# dual-led-wireless-dimmer-tx.net
KiCad netlist of a schematic drawn in EAGLE
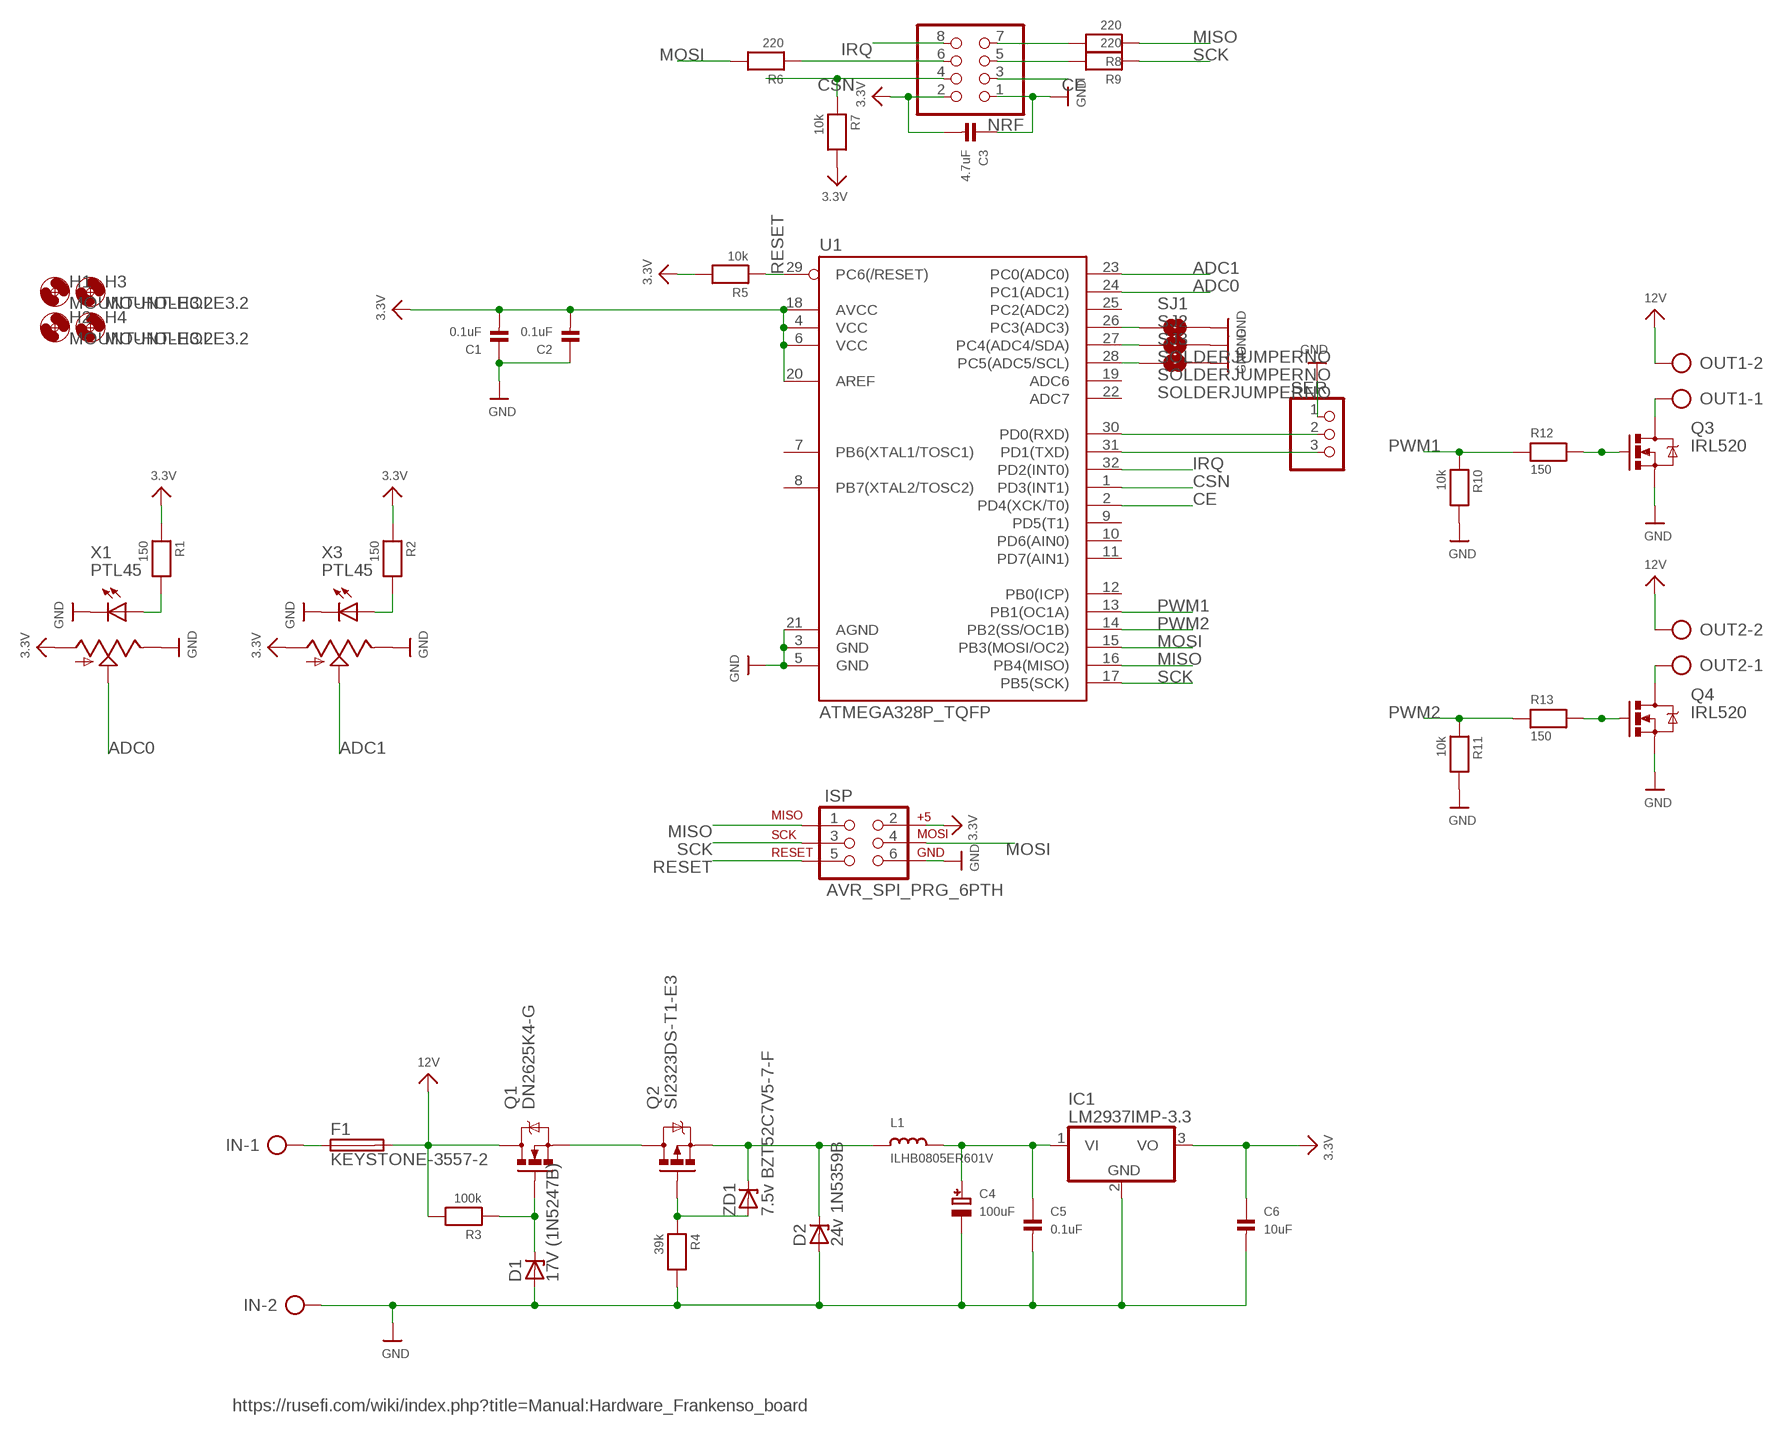
[diagram p0: schematic, sheet 1]

(export (version "E")
  (design (tool "Eeschema 10.0.6"))
  (components
    (comp (ref "C1")
      (value "0.1uF")
      (footprint "eagle-import:0805")
      (libsource (lib "eagle-import") (part "CAP_CERAMIC0805"))
    )
    (comp (ref "C2")
      (value "0.1uF")
      (footprint "eagle-import:0805")
      (libsource (lib "eagle-import") (part "CAP_CERAMIC0805"))
    )
    (comp (ref "C3")
      (value "4.7uF")
      (footprint "eagle-import:0805")
      (libsource (lib "eagle-import") (part "CAP_CERAMIC0805"))
    )
    (comp (ref "C4")
      (value "100uF")
      (footprint "eagle-import:PANASONIC_D")
      (libsource (lib "eagle-import") (part "CAP_ELECTROLYTICPANASONIC_D"))
    )
    (comp (ref "C5")
      (value "0.1uF")
      (footprint "eagle-import:0805")
      (libsource (lib "eagle-import") (part "CAP_CERAMIC0805"))
    )
    (comp (ref "C6")
      (value "10uF")
      (footprint "eagle-import:0805")
      (libsource (lib "eagle-import") (part "CAP_CERAMIC0805"))
    )
    (comp (ref "D1")
      (value "17V (1N5247B)")
      (footprint "eagle-import:ZDIO-5")
      (libsource (lib "eagle-import") (part "ZENER-DIODEZD-5"))
    )
    (comp (ref "D2")
      (value "24v 1N5359B")
      (footprint "eagle-import:DO41Z10")
      (libsource (lib "eagle-import") (part "ZPY"))
    )
    (comp (ref "F1")
      (value "KEYSTONE-3557-2")
      (footprint "eagle-import:KEYSTONE-3557-2")
      (libsource (lib "eagle-import") (part "KEYSTONE-3557-2"))
    )
    (comp (ref "H1")
      (value "MOUNT-HOLE3.2")
      (footprint "eagle-import:3,2")
      (libsource (lib "eagle-import") (part "MOUNT-HOLE3.2"))
    )
    (comp (ref "H2")
      (value "MOUNT-HOLE3.2")
      (footprint "eagle-import:3,2")
      (libsource (lib "eagle-import") (part "MOUNT-HOLE3.2"))
    )
    (comp (ref "H3")
      (value "MOUNT-HOLE3.2")
      (footprint "eagle-import:3,2")
      (libsource (lib "eagle-import") (part "MOUNT-HOLE3.2"))
    )
    (comp (ref "H4")
      (value "MOUNT-HOLE3.2")
      (footprint "eagle-import:3,2")
      (libsource (lib "eagle-import") (part "MOUNT-HOLE3.2"))
    )
    (comp (ref "IC1")
      (value "LM2937IMP-3.3")
      (footprint "eagle-import:TO263-3")
      (libsource (lib "eagle-import") (part "LM2937"))
    )
    (comp (ref "IN")
      (value "AK500/2-H")
      (footprint "eagle-import:AK500_2-H")
      (libsource (lib "eagle-import") (part "AK500/2-H"))
    )
    (comp (ref "ISP")
      (value "AVR_SPI_PRG_6PTH")
      (footprint "eagle-import:2X3")
      (libsource (lib "eagle-import") (part "AVR_SPI_PRG_6PTH"))
    )
    (comp (ref "L1")
      (value "ILHB0805ER601V")
      (footprint "eagle-import:0805")
      (libsource (lib "eagle-import") (part "INDUCTOR0805"))
    )
    (comp (ref "NRF")
      (value "PINHD-2X4")
      (footprint "eagle-import:2X04")
      (libsource (lib "eagle-import") (part "PINHD-2X4"))
    )
    (comp (ref "OUT1")
      (value "AK500/2-H")
      (footprint "eagle-import:AK500_2-H")
      (libsource (lib "eagle-import") (part "AK500/2-H"))
    )
    (comp (ref "OUT2")
      (value "AK500/2-H")
      (footprint "eagle-import:AK500_2-H")
      (libsource (lib "eagle-import") (part "AK500/2-H"))
    )
    (comp (ref "Q1")
      (value "DN2625K4-G")
      (footprint "eagle-import:DPAK")
      (libsource (lib "eagle-import") (part "MOSFET-NCHANNELFDD8780"))
    )
    (comp (ref "Q2")
      (value "SI2323DS-T1-E3")
      (footprint "eagle-import:SOT23-3")
      (libsource (lib "eagle-import") (part "MOSFET-PCHANNEL"))
    )
    (comp (ref "Q3")
      (value "IRL520")
      (footprint "eagle-import:TO220V")
      (libsource (lib "eagle-import") (part "keves-ng_1429743_MOSFET-NCHANNELFQP30N06L"))
    )
    (comp (ref "Q4")
      (value "IRL520")
      (footprint "eagle-import:TO220V")
      (libsource (lib "eagle-import") (part "keves-ng_1429743_MOSFET-NCHANNELFQP30N06L"))
    )
    (comp (ref "R1")
      (value "150")
      (footprint "eagle-import:0805")
      (libsource (lib "eagle-import") (part "RESISTOR0805"))
    )
    (comp (ref "R2")
      (value "150")
      (footprint "eagle-import:0805")
      (libsource (lib "eagle-import") (part "RESISTOR0805"))
    )
    (comp (ref "R3")
      (value "100k")
      (footprint "eagle-import:0805")
      (libsource (lib "eagle-import") (part "RESISTOR0805"))
    )
    (comp (ref "R4")
      (value "39k")
      (footprint "eagle-import:0805")
      (libsource (lib "eagle-import") (part "RESISTOR0805"))
    )
    (comp (ref "R5")
      (value "10k")
      (footprint "eagle-import:0805")
      (libsource (lib "eagle-import") (part "RESISTOR0805"))
    )
    (comp (ref "R6")
      (value "220")
      (footprint "eagle-import:0805")
      (libsource (lib "eagle-import") (part "RESISTOR0805"))
    )
    (comp (ref "R7")
      (value "10k")
      (footprint "eagle-import:0805")
      (libsource (lib "eagle-import") (part "RESISTOR0805"))
    )
    (comp (ref "R8")
      (value "220")
      (footprint "eagle-import:0805")
      (libsource (lib "eagle-import") (part "RESISTOR0805"))
    )
    (comp (ref "R9")
      (value "220")
      (footprint "eagle-import:0805")
      (libsource (lib "eagle-import") (part "RESISTOR0805"))
    )
    (comp (ref "R10")
      (value "10k")
      (footprint "eagle-import:0805")
      (libsource (lib "eagle-import") (part "RESISTOR0805"))
    )
    (comp (ref "R11")
      (value "10k")
      (footprint "eagle-import:0805")
      (libsource (lib "eagle-import") (part "RESISTOR0805"))
    )
    (comp (ref "R12")
      (value "150")
      (footprint "eagle-import:0805")
      (libsource (lib "eagle-import") (part "RESISTOR0805"))
    )
    (comp (ref "R13")
      (value "150")
      (footprint "eagle-import:0805")
      (libsource (lib "eagle-import") (part "RESISTOR0805"))
    )
    (comp (ref "SER")
      (value "PINHD-1X3")
      (footprint "eagle-import:1X03")
      (libsource (lib "eagle-import") (part "PINHD-1X3"))
    )
    (comp (ref "SJ1")
      (value "SOLDERJUMPERNO")
      (footprint "eagle-import:SJ_2S-NO")
      (libsource (lib "eagle-import") (part "SOLDERJUMPERNO"))
    )
    (comp (ref "SJ2")
      (value "SOLDERJUMPERNO")
      (footprint "eagle-import:SJ_2S-NO")
      (libsource (lib "eagle-import") (part "SOLDERJUMPERNO"))
    )
    (comp (ref "SJ3")
      (value "SOLDERJUMPERNO")
      (footprint "eagle-import:SJ_2S-NO")
      (libsource (lib "eagle-import") (part "SOLDERJUMPERNO"))
    )
    (comp (ref "U1")
      (value "ATMEGA328P_TQFP")
      (footprint "eagle-import:TQFP32-08")
      (libsource (lib "eagle-import") (part "ATMEGA328P_TQFP"))
    )
    (comp (ref "X1")
      (value "PTL45")
      (footprint "eagle-import:BOURNS-PTL45")
      (fields (field (name "SPICEPREFIX") "C"))
      (libsource (lib "eagle-import") (part "PTL45"))
    )
    (comp (ref "X3")
      (value "PTL45")
      (footprint "eagle-import:BOURNS-PTL45")
      (libsource (lib "eagle-import") (part "PTL45"))
    )
    (comp (ref "ZD1")
      (value "7.5v BZT52C7V5-7-F")
      (footprint "eagle-import:SOD123")
      (libsource (lib "eagle-import") (part "ZD-SOD123"))
    )
  )
  (nets
    (net (code "1") (name "/ADC0") (class "Default")
      (node (ref "U1") (pin "24") (pinfunction "PC1(ADC1)_24") (pintype "bidirectional"))
      (node (ref "X1") (pin "2") (pinfunction "S_2") (pintype "passive"))
    )
    (net (code "2") (name "/ADC1") (class "Default")
      (node (ref "U1") (pin "23") (pinfunction "PC0(ADC0)_23") (pintype "bidirectional"))
      (node (ref "X3") (pin "2") (pinfunction "S_2") (pintype "passive"))
    )
    (net (code "3") (name "/CE") (class "Default")
      (node (ref "NRF") (pin "3") (pinfunction "3_3") (pintype "passive"))
      (node (ref "U1") (pin "2") (pinfunction "PD4(XCK/T0)_2") (pintype "bidirectional"))
    )
    (net (code "4") (name "/CSN") (class "Default")
      (node (ref "NRF") (pin "4") (pinfunction "4_4") (pintype "passive"))
      (node (ref "R7") (pin "1") (pinfunction "1_1") (pintype "passive"))
      (node (ref "U1") (pin "1") (pinfunction "PD3(INT1)_1") (pintype "bidirectional"))
    )
    (net (code "5") (name "/IRQ") (class "Default")
      (node (ref "NRF") (pin "8") (pinfunction "8_8") (pintype "passive"))
      (node (ref "U1") (pin "32") (pinfunction "PD2(INT0)_32") (pintype "bidirectional"))
    )
    (net (code "6") (name "/MISO") (class "Default")
      (node (ref "ISP") (pin "1") (pinfunction "1_1") (pintype "passive"))
      (node (ref "R8") (pin "1") (pinfunction "1_1") (pintype "passive"))
      (node (ref "U1") (pin "16") (pinfunction "PB4(MISO)_16") (pintype "bidirectional"))
    )
    (net (code "7") (name "/MOSI") (class "Default")
      (node (ref "ISP") (pin "4") (pinfunction "4_4") (pintype "passive"))
      (node (ref "R6") (pin "2") (pinfunction "2_2") (pintype "passive"))
      (node (ref "U1") (pin "15") (pinfunction "PB3(MOSI/OC2)_15") (pintype "bidirectional"))
    )
    (net (code "8") (name "/PWM1") (class "Default")
      (node (ref "R10") (pin "1") (pinfunction "1_1") (pintype "passive"))
      (node (ref "R12") (pin "1") (pinfunction "1_1") (pintype "passive"))
      (node (ref "U1") (pin "13") (pinfunction "PB1(OC1A)_13") (pintype "bidirectional"))
    )
    (net (code "9") (name "/PWM2") (class "Default")
      (node (ref "R11") (pin "1") (pinfunction "1_1") (pintype "passive"))
      (node (ref "R13") (pin "1") (pinfunction "1_1") (pintype "passive"))
      (node (ref "U1") (pin "14") (pinfunction "PB2(SS/OC1B)_14") (pintype "bidirectional"))
    )
    (net (code "10") (name "/RESET") (class "Default")
      (node (ref "ISP") (pin "5") (pinfunction "5_5") (pintype "passive"))
      (node (ref "R5") (pin "1") (pinfunction "1_1") (pintype "passive"))
      (node (ref "U1") (pin "29") (pinfunction "PC6(/RESET)_29") (pintype "bidirectional"))
    )
    (net (code "11") (name "/SCK") (class "Default")
      (node (ref "ISP") (pin "3") (pinfunction "3_3") (pintype "passive"))
      (node (ref "R9") (pin "1") (pinfunction "1_1") (pintype "passive"))
      (node (ref "U1") (pin "17") (pinfunction "PB5(SCK)_17") (pintype "bidirectional"))
    )
    (net (code "12") (name "3.3V") (class "Default")
      (node (ref "C1") (pin "2") (pinfunction "P$2_2") (pintype "passive"))
      (node (ref "C2") (pin "2") (pinfunction "P$2_2") (pintype "passive"))
      (node (ref "C3") (pin "2") (pinfunction "P$2_2") (pintype "passive"))
      (node (ref "C6") (pin "1") (pinfunction "P$1_1") (pintype "passive"))
      (node (ref "IC1") (pin "3") (pinfunction "VO_3") (pintype "passive"))
      (node (ref "ISP") (pin "2") (pinfunction "2_2") (pintype "passive"))
      (node (ref "NRF") (pin "2") (pinfunction "2_2") (pintype "passive"))
      (node (ref "R1") (pin "1") (pinfunction "1_1") (pintype "passive"))
      (node (ref "R2") (pin "1") (pinfunction "1_1") (pintype "passive"))
      (node (ref "R5") (pin "2") (pinfunction "2_2") (pintype "passive"))
      (node (ref "R7") (pin "2") (pinfunction "2_2") (pintype "passive"))
      (node (ref "U1") (pin "18") (pinfunction "AVCC_18") (pintype "bidirectional"))
      (node (ref "U1") (pin "20") (pinfunction "AREF_20") (pintype "bidirectional"))
      (node (ref "U1") (pin "4") (pinfunction "VCC_4") (pintype "bidirectional"))
      (node (ref "U1") (pin "6") (pinfunction "VCC_6") (pintype "bidirectional"))
      (node (ref "X1") (pin "1") (pinfunction "A_1") (pintype "passive"))
      (node (ref "X3") (pin "1") (pinfunction "A_1") (pintype "passive"))
    )
    (net (code "13") (name "12V") (class "Default")
      (node (ref "F1") (pin "R1") (pinfunction "2_R1") (pintype "passive"))
      (node (ref "F1") (pin "R2") (pinfunction "2_R2") (pintype "passive"))
      (node (ref "OUT1") (pin "2") (pinfunction "KL_2") (pintype "passive"))
      (node (ref "OUT2") (pin "2") (pinfunction "KL_2") (pintype "passive"))
      (node (ref "Q1") (pin "4") (pinfunction "D_4") (pintype "passive"))
      (node (ref "R3") (pin "2") (pinfunction "2_2") (pintype "passive"))
    )
    (net (code "14") (name "GND") (class "Default")
      (node (ref "C1") (pin "1") (pinfunction "P$1_1") (pintype "passive"))
      (node (ref "C2") (pin "1") (pinfunction "P$1_1") (pintype "passive"))
      (node (ref "C3") (pin "1") (pinfunction "P$1_1") (pintype "passive"))
      (node (ref "C4") (pin "-") (pinfunction "-_-") (pintype "passive"))
      (node (ref "C5") (pin "2") (pinfunction "P$2_2") (pintype "passive"))
      (node (ref "C6") (pin "2") (pinfunction "P$2_2") (pintype "passive"))
      (node (ref "D1") (pin "A") (pinfunction "A_A") (pintype "passive"))
      (node (ref "D2") (pin "A") (pinfunction "A_A") (pintype "passive"))
      (node (ref "IC1") (pin "2") (pinfunction "GND_2") (pintype "passive"))
      (node (ref "IN") (pin "2") (pinfunction "KL_2") (pintype "passive"))
      (node (ref "ISP") (pin "6") (pinfunction "6_6") (pintype "passive"))
      (node (ref "NRF") (pin "1") (pinfunction "1_1") (pintype "passive"))
      (node (ref "Q3") (pin "3") (pinfunction "S_3") (pintype "passive"))
      (node (ref "Q4") (pin "3") (pinfunction "S_3") (pintype "passive"))
      (node (ref "R10") (pin "2") (pinfunction "2_2") (pintype "passive"))
      (node (ref "R11") (pin "2") (pinfunction "2_2") (pintype "passive"))
      (node (ref "R4") (pin "2") (pinfunction "2_2") (pintype "passive"))
      (node (ref "SER") (pin "1") (pinfunction "1_1") (pintype "passive"))
      (node (ref "SJ1") (pin "2") (pinfunction "2_2") (pintype "passive"))
      (node (ref "SJ2") (pin "2") (pinfunction "2_2") (pintype "passive"))
      (node (ref "SJ3") (pin "2") (pinfunction "2_2") (pintype "passive"))
      (node (ref "U1") (pin "21") (pinfunction "AGND_21") (pintype "bidirectional"))
      (node (ref "U1") (pin "3") (pinfunction "GND_3") (pintype "bidirectional"))
      (node (ref "U1") (pin "5") (pinfunction "GND_5") (pintype "bidirectional"))
      (node (ref "X1") (pin "3") (pinfunction "E_3") (pintype "passive"))
      (node (ref "X1") (pin "E") (pinfunction "LED-_E") (pintype "passive"))
      (node (ref "X3") (pin "3") (pinfunction "E_3") (pintype "passive"))
      (node (ref "X3") (pin "E") (pinfunction "LED-_E") (pintype "passive"))
    )
    (net (code "15") (name "Net-(C5-P$1)") (class "Default")
      (node (ref "C4") (pin "+") (pinfunction "+_+") (pintype "passive"))
      (node (ref "C5") (pin "1") (pinfunction "P$1_1") (pintype "passive"))
      (node (ref "IC1") (pin "1") (pinfunction "VI_1") (pintype "input"))
      (node (ref "L1") (pin "2") (pinfunction "2_2") (pintype "passive"))
    )
    (net (code "16") (name "Net-(INA-KL)") (class "Default")
      (node (ref "F1") (pin "L1") (pinfunction "1_L1") (pintype "passive"))
      (node (ref "F1") (pin "L2") (pinfunction "1_L2") (pintype "passive"))
      (node (ref "IN") (pin "1") (pinfunction "KL_1") (pintype "passive"))
    )
    (net (code "17") (name "Net-(NRF-Pad5)") (class "Default")
      (node (ref "NRF") (pin "5") (pinfunction "5_5") (pintype "passive"))
      (node (ref "R9") (pin "2") (pinfunction "2_2") (pintype "passive"))
    )
    (net (code "18") (name "Net-(NRF-Pad6)") (class "Default")
      (node (ref "NRF") (pin "6") (pinfunction "6_6") (pintype "passive"))
      (node (ref "R6") (pin "1") (pinfunction "1_1") (pintype "passive"))
    )
    (net (code "19") (name "Net-(NRF-Pad7)") (class "Default")
      (node (ref "NRF") (pin "7") (pinfunction "7_7") (pintype "passive"))
      (node (ref "R8") (pin "2") (pinfunction "2_2") (pintype "passive"))
    )
    (net (code "20") (name "Net-(OUT1A-KL)") (class "Default")
      (node (ref "OUT1") (pin "1") (pinfunction "KL_1") (pintype "passive"))
      (node (ref "Q3") (pin "2") (pinfunction "D_2") (pintype "passive"))
    )
    (net (code "21") (name "Net-(OUT2A-KL)") (class "Default")
      (node (ref "OUT2") (pin "1") (pinfunction "KL_1") (pintype "passive"))
      (node (ref "Q4") (pin "2") (pinfunction "D_2") (pintype "passive"))
    )
    (net (code "22") (name "Net-(Q1-G)") (class "Default")
      (node (ref "D1") (pin "C") (pinfunction "C_C") (pintype "passive"))
      (node (ref "Q1") (pin "1") (pinfunction "G_1") (pintype "passive"))
      (node (ref "R3") (pin "1") (pinfunction "1_1") (pintype "passive"))
    )
    (net (code "23") (name "Net-(Q1-S)") (class "Default")
      (node (ref "Q1") (pin "3") (pinfunction "S_3") (pintype "passive"))
      (node (ref "Q2") (pin "3") (pinfunction "D_3") (pintype "passive"))
    )
    (net (code "24") (name "Net-(Q2-G)") (class "Default")
      (node (ref "Q2") (pin "1") (pinfunction "G_1") (pintype "passive"))
      (node (ref "R4") (pin "1") (pinfunction "1_1") (pintype "passive"))
      (node (ref "ZD1") (pin "A") (pinfunction "A_A") (pintype "passive"))
    )
    (net (code "25") (name "Net-(Q2-S)") (class "Default")
      (node (ref "D2") (pin "C") (pinfunction "C_C") (pintype "passive"))
      (node (ref "L1") (pin "1") (pinfunction "1_1") (pintype "passive"))
      (node (ref "Q2") (pin "2") (pinfunction "S_2") (pintype "passive"))
      (node (ref "ZD1") (pin "C") (pinfunction "C_C") (pintype "passive"))
    )
    (net (code "26") (name "Net-(Q3-G)") (class "Default")
      (node (ref "Q3") (pin "1") (pinfunction "G_1") (pintype "passive"))
      (node (ref "R12") (pin "2") (pinfunction "2_2") (pintype "passive"))
    )
    (net (code "27") (name "Net-(Q4-G)") (class "Default")
      (node (ref "Q4") (pin "1") (pinfunction "G_1") (pintype "passive"))
      (node (ref "R13") (pin "2") (pinfunction "2_2") (pintype "passive"))
    )
    (net (code "28") (name "Net-(U1-PC3(ADC3))") (class "Default")
      (node (ref "SJ1") (pin "1") (pinfunction "1_1") (pintype "passive"))
      (node (ref "U1") (pin "26") (pinfunction "PC3(ADC3)_26") (pintype "bidirectional"))
    )
    (net (code "29") (name "Net-(U1-PC4(ADC4{slash}SDA))") (class "Default")
      (node (ref "SJ2") (pin "1") (pinfunction "1_1") (pintype "passive"))
      (node (ref "U1") (pin "27") (pinfunction "PC4(ADC4/SDA)_27") (pintype "bidirectional"))
    )
    (net (code "30") (name "Net-(U1-PC5(ADC5{slash}SCL))") (class "Default")
      (node (ref "SJ3") (pin "1") (pinfunction "1_1") (pintype "passive"))
      (node (ref "U1") (pin "28") (pinfunction "PC5(ADC5/SCL)_28") (pintype "bidirectional"))
    )
    (net (code "31") (name "Net-(U1-PD0(RXD))") (class "Default")
      (node (ref "SER") (pin "2") (pinfunction "2_2") (pintype "passive"))
      (node (ref "U1") (pin "30") (pinfunction "PD0(RXD)_30") (pintype "bidirectional"))
    )
    (net (code "32") (name "Net-(U1-PD1(TXD))") (class "Default")
      (node (ref "SER") (pin "3") (pinfunction "3_3") (pintype "passive"))
      (node (ref "U1") (pin "31") (pinfunction "PD1(TXD)_31") (pintype "bidirectional"))
    )
    (net (code "33") (name "Net-(X1-LED+)") (class "Default")
      (node (ref "R1") (pin "2") (pinfunction "2_2") (pintype "passive"))
      (node (ref "X1") (pin "B") (pinfunction "LED+_B") (pintype "passive"))
    )
    (net (code "34") (name "Net-(X3-LED+)") (class "Default")
      (node (ref "R2") (pin "2") (pinfunction "2_2") (pintype "passive"))
      (node (ref "X3") (pin "B") (pinfunction "LED+_B") (pintype "passive"))
    )
    (net (code "35") (name "unconnected-(U1-ADC6-Pad19)") (class "Default")
      (node (ref "U1") (pin "19") (pinfunction "ADC6_19") (pintype "bidirectional"))
    )
    (net (code "36") (name "unconnected-(U1-ADC7-Pad22)") (class "Default")
      (node (ref "U1") (pin "22") (pinfunction "ADC7_22") (pintype "bidirectional"))
    )
    (net (code "37") (name "unconnected-(U1-PB0(ICP)-Pad12)") (class "Default")
      (node (ref "U1") (pin "12") (pinfunction "PB0(ICP)_12") (pintype "bidirectional"))
    )
    (net (code "38") (name "unconnected-(U1-PB6(XTAL1{slash}TOSC1)-Pad7)") (class "Default")
      (node (ref "U1") (pin "7") (pinfunction "PB6(XTAL1/TOSC1)_7") (pintype "bidirectional"))
    )
    (net (code "39") (name "unconnected-(U1-PB7(XTAL2{slash}TOSC2)-Pad8)") (class "Default")
      (node (ref "U1") (pin "8") (pinfunction "PB7(XTAL2/TOSC2)_8") (pintype "bidirectional"))
    )
    (net (code "40") (name "unconnected-(U1-PC2(ADC2)-Pad25)") (class "Default")
      (node (ref "U1") (pin "25") (pinfunction "PC2(ADC2)_25") (pintype "bidirectional"))
    )
    (net (code "41") (name "unconnected-(U1-PD5(T1)-Pad9)") (class "Default")
      (node (ref "U1") (pin "9") (pinfunction "PD5(T1)_9") (pintype "bidirectional"))
    )
    (net (code "42") (name "unconnected-(U1-PD6(AIN0)-Pad10)") (class "Default")
      (node (ref "U1") (pin "10") (pinfunction "PD6(AIN0)_10") (pintype "bidirectional"))
    )
    (net (code "43") (name "unconnected-(U1-PD7(AIN1)-Pad11)") (class "Default")
      (node (ref "U1") (pin "11") (pinfunction "PD7(AIN1)_11") (pintype "bidirectional"))
    )
  )
)
